# EnsembleThree.net
KiCad netlist of a schematic drawn in EAGLE
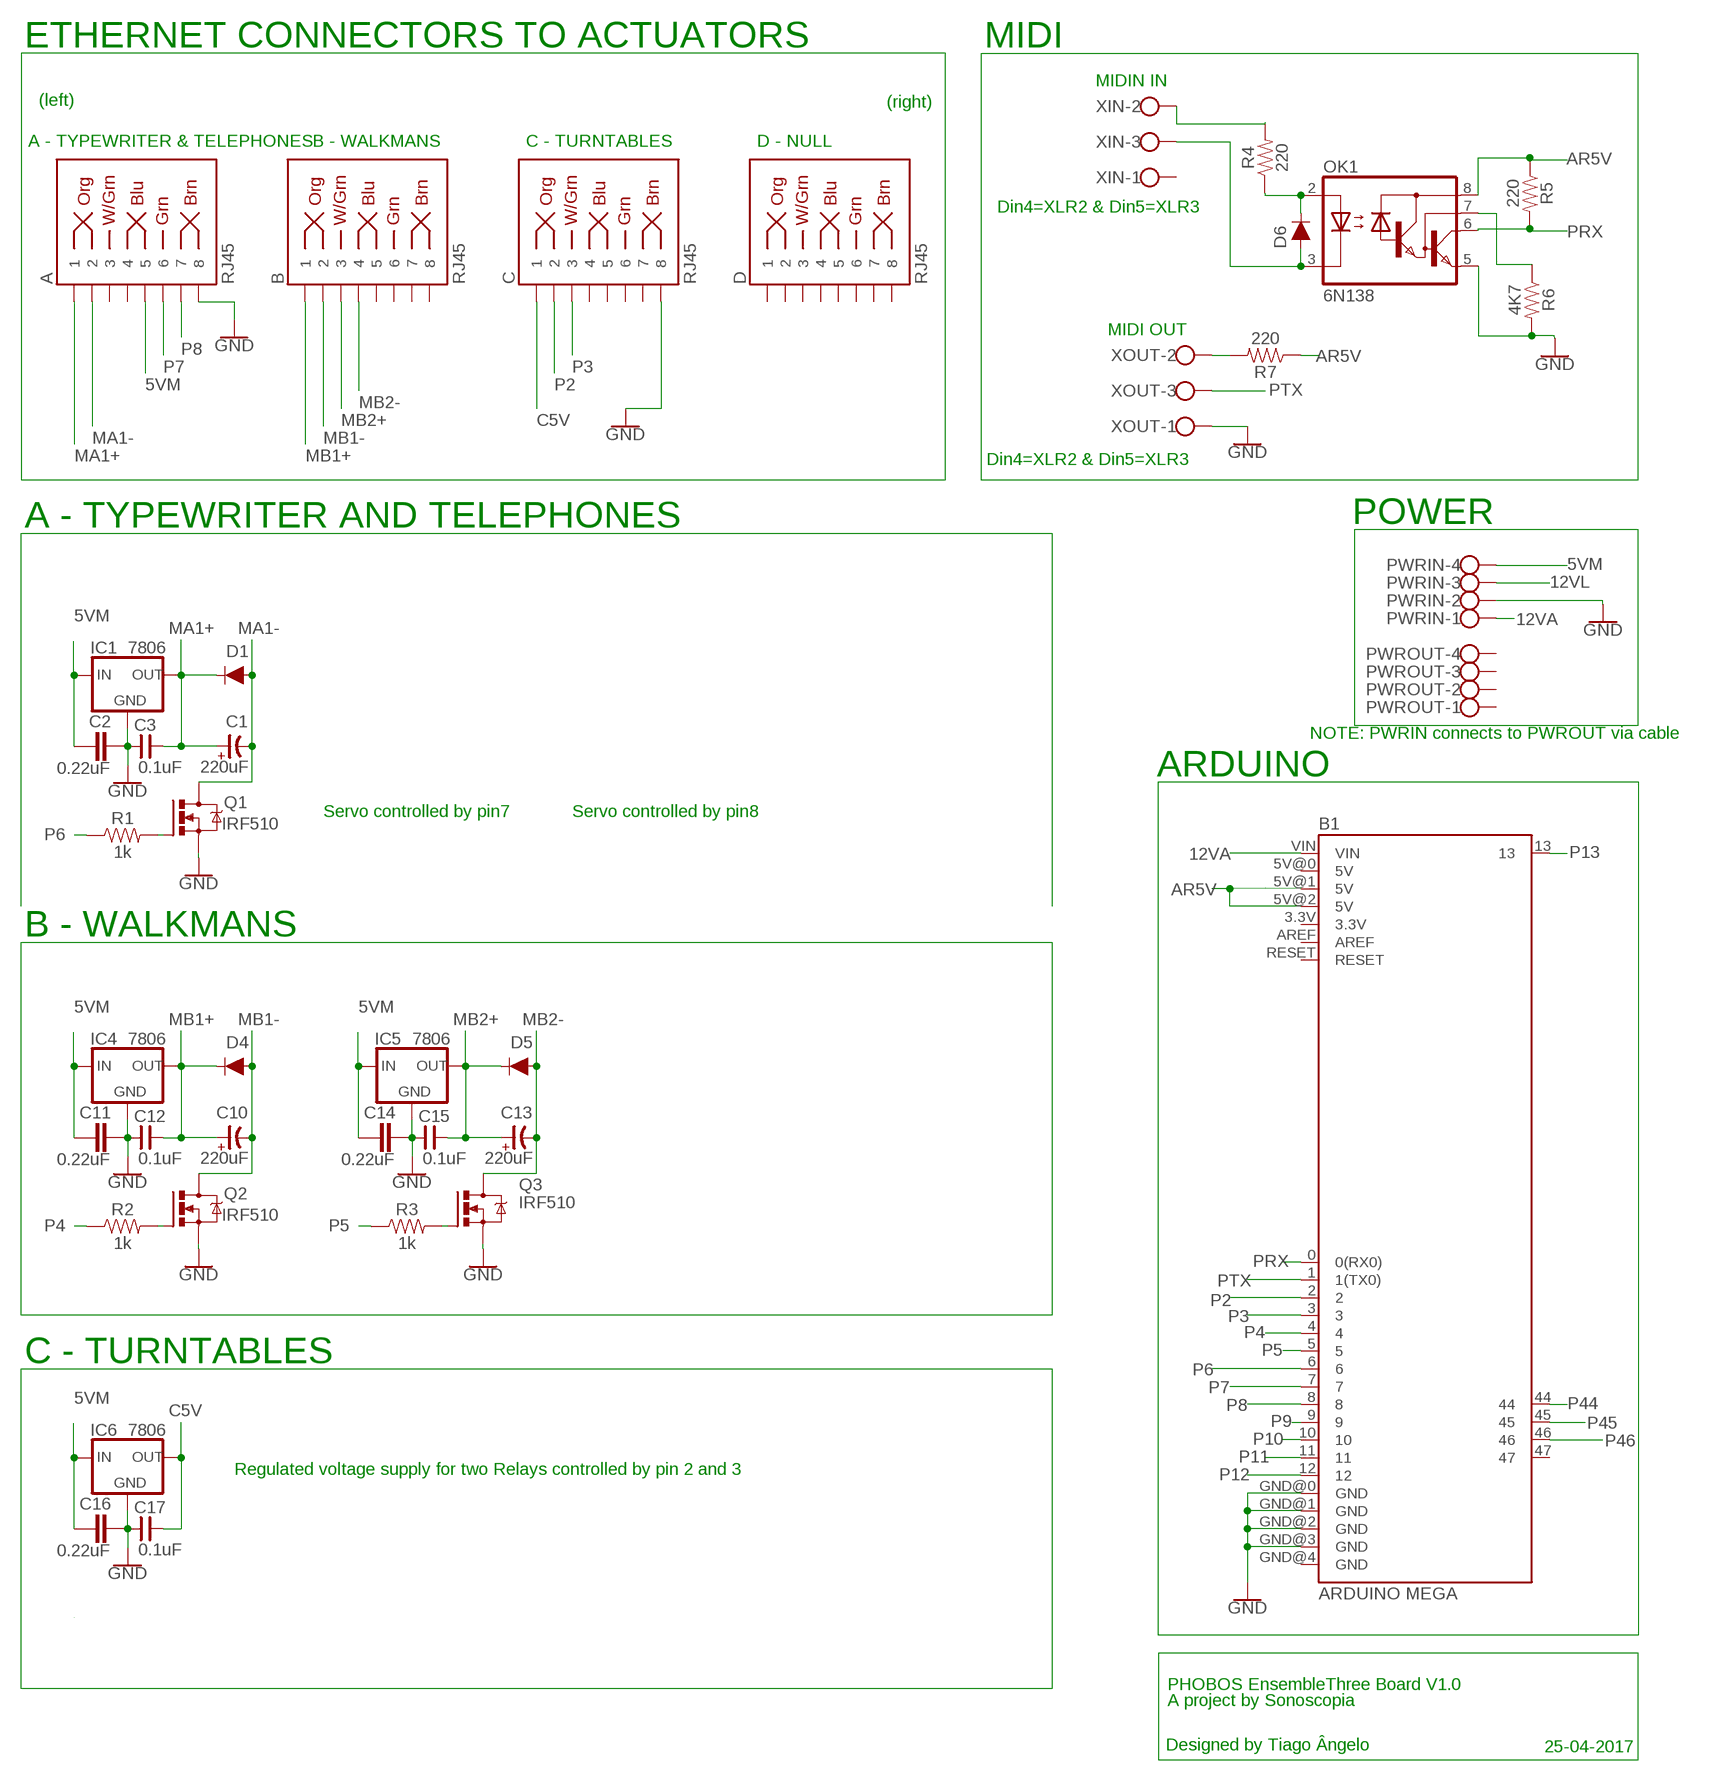
[diagram p0: schematic, sheet 1]

(export (version "E")
  (design (tool "Eeschema 10.0.6"))
  (components
    (comp (ref "A")
      (value "RJ45")
      (footprint "eagle-import:RJ45-8")
      (libsource (lib "eagle-import") (part "RJ45-8"))
    )
    (comp (ref "B")
      (value "RJ45")
      (footprint "eagle-import:RJ45-8")
      (libsource (lib "eagle-import") (part "RJ45-8"))
    )
    (comp (ref "B1")
      (value "ARDUINO MEGA")
      (footprint "eagle-import:ARDUINO_MEGA")
      (libsource (lib "eagle-import") (part "ARDUINO_MEGA_R3FULL"))
    )
    (comp (ref "C")
      (value "RJ45")
      (footprint "eagle-import:RJ45-8")
      (libsource (lib "eagle-import") (part "RJ45-8"))
    )
    (comp (ref "C1")
      (value "220uF")
      (footprint "eagle-import:E-035X080")
      (libsource (lib "eagle-import") (part "CP-E-035X080"))
    )
    (comp (ref "C2")
      (value "0.22uF")
      (footprint "eagle-import:C5B3")
      (libsource (lib "eagle-import") (part "C5/3"))
    )
    (comp (ref "C3")
      (value "0.1uF")
      (footprint "eagle-import:C025-050X025")
      (libsource (lib "eagle-import") (part "CNP-C025-050X025"))
    )
    (comp (ref "C10")
      (value "220uF")
      (footprint "eagle-import:E-035X080")
      (libsource (lib "eagle-import") (part "CP-E-035X080"))
    )
    (comp (ref "C11")
      (value "0.22uF")
      (footprint "eagle-import:C5B3")
      (libsource (lib "eagle-import") (part "C5/3"))
    )
    (comp (ref "C12")
      (value "0.1uF")
      (footprint "eagle-import:C025-050X025")
      (libsource (lib "eagle-import") (part "CNP-C025-050X025"))
    )
    (comp (ref "C13")
      (value "220uF")
      (footprint "eagle-import:CAP-MASTER_E-035X080")
      (libsource (lib "eagle-import") (part "CAP-MASTER_CP-E-035X080"))
    )
    (comp (ref "C14")
      (value "0.22uF")
      (footprint "eagle-import:C5B3")
      (libsource (lib "eagle-import") (part "C5/3"))
    )
    (comp (ref "C15")
      (value "0.1uF")
      (footprint "eagle-import:C025-050X025")
      (libsource (lib "eagle-import") (part "CNP-C025-050X025"))
    )
    (comp (ref "C16")
      (value "0.22uF")
      (footprint "eagle-import:C5B3")
      (libsource (lib "eagle-import") (part "C5/3"))
    )
    (comp (ref "C17")
      (value "0.1uF")
      (footprint "eagle-import:C025-050X025")
      (libsource (lib "eagle-import") (part "CNP-C025-050X025"))
    )
    (comp (ref "D")
      (value "RJ45")
      (footprint "eagle-import:RJ45-8")
      (libsource (lib "eagle-import") (part "RJ45-8"))
    )
    (comp (ref "D1")
      (value "1A/50V/1.1V")
      (footprint "eagle-import:DIODE-1N4001-KIT")
      (libsource (lib "eagle-import") (part "DIODE-KIT2"))
    )
    (comp (ref "D4")
      (value "1A/50V/1.1V")
      (footprint "eagle-import:DIODE-1N4001-KIT")
      (libsource (lib "eagle-import") (part "DIODE-KIT2"))
    )
    (comp (ref "D5")
      (value "1A/50V/1.1V")
      (footprint "eagle-import:DIODE-1N4001-KIT")
      (libsource (lib "eagle-import") (part "DIODE-KIT2"))
    )
    (comp (ref "D6")
      (value "200mA/100V/1V")
      (footprint "eagle-import:DIODE-1N4148")
      (libsource (lib "eagle-import") (part "DIODE-1N4148"))
    )
    (comp (ref "IC1")
      (value "7806")
      (footprint "eagle-import:78XXS")
      (libsource (lib "eagle-import") (part "78XXS"))
    )
    (comp (ref "IC4")
      (value "7806")
      (footprint "eagle-import:78XXS")
      (libsource (lib "eagle-import") (part "78XXS"))
    )
    (comp (ref "IC5")
      (value "7806")
      (footprint "eagle-import:78XXS")
      (libsource (lib "eagle-import") (part "78XXS"))
    )
    (comp (ref "IC6")
      (value "7806")
      (footprint "eagle-import:78XXS")
      (libsource (lib "eagle-import") (part "78XXS"))
    )
    (comp (ref "OK1")
      (value "6N138")
      (footprint "eagle-import:DIL08")
      (fields (field (name "MF") "VISHAY/TELEFUNKEN"))
      (libsource (lib "eagle-import") (part "6N138"))
    )
    (comp (ref "PWRIN")
      (value "W237-4")
      (footprint "eagle-import:W237-4")
      (libsource (lib "eagle-import") (part "W237-4"))
    )
    (comp (ref "PWROUT")
      (value "W237-4")
      (footprint "eagle-import:W237-4")
      (libsource (lib "eagle-import") (part "W237-4"))
    )
    (comp (ref "Q1")
      (value "IRF510")
      (footprint "eagle-import:TO220BV")
      (libsource (lib "eagle-import") (part "IRF520"))
    )
    (comp (ref "Q2")
      (value "IRF510")
      (footprint "eagle-import:TO220BV")
      (libsource (lib "eagle-import") (part "IRF520"))
    )
    (comp (ref "Q3")
      (value "IRF510")
      (footprint "eagle-import:TRANSISTOR-POWER_TO220BV")
      (libsource (lib "eagle-import") (part "TRANSISTOR-POWER_IRF520"))
    )
    (comp (ref "R1")
      (value "1k")
      (footprint "eagle-import:AXIAL-0.1")
      (libsource (lib "eagle-import") (part "1KOHM-VERT-1/4W-1%"))
    )
    (comp (ref "R2")
      (value "1k")
      (footprint "eagle-import:AXIAL-0.1")
      (libsource (lib "eagle-import") (part "1KOHM-VERT-1/4W-1%"))
    )
    (comp (ref "R3")
      (value "1k")
      (footprint "eagle-import:AXIAL-0.1")
      (libsource (lib "eagle-import") (part "1KOHM-VERT-1/4W-1%"))
    )
    (comp (ref "R4")
      (value "220")
      (footprint "eagle-import:AXIAL-0.3")
      (libsource (lib "eagle-import") (part "1KOHM-HORIZ-1/4W-5%"))
    )
    (comp (ref "R5")
      (value "220")
      (footprint "eagle-import:AXIAL-0.3")
      (libsource (lib "eagle-import") (part "1KOHM-HORIZ-1/4W-5%"))
    )
    (comp (ref "R6")
      (value "4K7")
      (footprint "eagle-import:AXIAL-0.3")
      (libsource (lib "eagle-import") (part "1KOHM-HORIZ-1/4W-5%"))
    )
    (comp (ref "R7")
      (value "220")
      (footprint "eagle-import:AXIAL-0.3")
      (libsource (lib "eagle-import") (part "1KOHM-HORIZ-1/4W-5%"))
    )
    (comp (ref "XIN")
      (value "W237-103")
      (footprint "eagle-import:W237-103")
      (fields (field (name "MPN") "237-103"))
      (libsource (lib "eagle-import") (part "W237-103"))
    )
    (comp (ref "XOUT")
      (value "W237-103")
      (footprint "eagle-import:W237-103")
      (fields (field (name "MPN") "237-103"))
      (libsource (lib "eagle-import") (part "W237-103"))
    )
  )
  (nets
    (net (code "1") (name "/5VM") (class "Default")
      (node (ref "A") (pin "5") (pinfunction "5_5") (pintype "bidirectional"))
      (node (ref "C11") (pin "1") (pinfunction "1_1") (pintype "passive"))
      (node (ref "C14") (pin "1") (pinfunction "1_1") (pintype "passive"))
      (node (ref "C16") (pin "1") (pinfunction "1_1") (pintype "passive"))
      (node (ref "C2") (pin "1") (pinfunction "1_1") (pintype "passive"))
      (node (ref "IC1") (pin "IN") (pinfunction "IN_IN") (pintype "input"))
      (node (ref "IC4") (pin "IN") (pinfunction "IN_IN") (pintype "input"))
      (node (ref "IC5") (pin "IN") (pinfunction "IN_IN") (pintype "input"))
      (node (ref "IC6") (pin "IN") (pinfunction "IN_IN") (pintype "input"))
      (node (ref "PWRIN") (pin "4") (pinfunction "KL_4") (pintype "passive"))
    )
    (net (code "2") (name "/12VA") (class "Default")
      (node (ref "B1") (pin "VIN") (pinfunction "VIN_VIN") (pintype "bidirectional"))
      (node (ref "PWRIN") (pin "1") (pinfunction "KL_1") (pintype "passive"))
    )
    (net (code "3") (name "/12VL") (class "Default")
      (node (ref "PWRIN") (pin "3") (pinfunction "KL_3") (pintype "passive"))
    )
    (net (code "4") (name "/AR5V") (class "Default")
      (node (ref "B1") (pin "5V@1") (pinfunction "5V_5V@1") (pintype "bidirectional"))
      (node (ref "B1") (pin "5V@2") (pinfunction "5V_5V@2") (pintype "bidirectional"))
      (node (ref "OK1") (pin "8") (pinfunction "VCC_8") (pintype "passive"))
      (node (ref "R5") (pin "P$1") (pinfunction "1_P$1") (pintype "passive"))
      (node (ref "R7") (pin "P$1") (pinfunction "1_P$1") (pintype "passive"))
    )
    (net (code "5") (name "/C5V") (class "Default")
      (node (ref "C") (pin "1") (pinfunction "1_1") (pintype "bidirectional"))
      (node (ref "C17") (pin "2") (pinfunction "2_2") (pintype "passive"))
      (node (ref "IC6") (pin "OUT") (pinfunction "OUT_OUT") (pintype "passive"))
    )
    (net (code "6") (name "/MA1+") (class "Default")
      (node (ref "A") (pin "1") (pinfunction "1_1") (pintype "bidirectional"))
      (node (ref "C1") (pin "+") (pinfunction "+_+") (pintype "passive"))
      (node (ref "C3") (pin "2") (pinfunction "2_2") (pintype "passive"))
      (node (ref "D1") (pin "C") (pinfunction "C_C") (pintype "passive"))
      (node (ref "IC1") (pin "OUT") (pinfunction "OUT_OUT") (pintype "passive"))
    )
    (net (code "7") (name "/MA1-") (class "Default")
      (node (ref "A") (pin "2") (pinfunction "2_2") (pintype "bidirectional"))
      (node (ref "C1") (pin "-") (pinfunction "-_-") (pintype "passive"))
      (node (ref "D1") (pin "A") (pinfunction "A_A") (pintype "passive"))
      (node (ref "Q1") (pin "D") (pinfunction "D_D") (pintype "passive"))
    )
    (net (code "8") (name "/MB1+") (class "Default")
      (node (ref "B") (pin "1") (pinfunction "1_1") (pintype "bidirectional"))
      (node (ref "C10") (pin "+") (pinfunction "+_+") (pintype "passive"))
      (node (ref "C12") (pin "2") (pinfunction "2_2") (pintype "passive"))
      (node (ref "D4") (pin "C") (pinfunction "C_C") (pintype "passive"))
      (node (ref "IC4") (pin "OUT") (pinfunction "OUT_OUT") (pintype "passive"))
    )
    (net (code "9") (name "/MB1-") (class "Default")
      (node (ref "B") (pin "2") (pinfunction "2_2") (pintype "bidirectional"))
      (node (ref "C10") (pin "-") (pinfunction "-_-") (pintype "passive"))
      (node (ref "D4") (pin "A") (pinfunction "A_A") (pintype "passive"))
      (node (ref "Q2") (pin "D") (pinfunction "D_D") (pintype "passive"))
    )
    (net (code "10") (name "/MB2+") (class "Default")
      (node (ref "B") (pin "3") (pinfunction "3_3") (pintype "bidirectional"))
      (node (ref "C13") (pin "+") (pinfunction "+_+") (pintype "passive"))
      (node (ref "C15") (pin "2") (pinfunction "2_2") (pintype "passive"))
      (node (ref "D5") (pin "C") (pinfunction "C_C") (pintype "passive"))
      (node (ref "IC5") (pin "OUT") (pinfunction "OUT_OUT") (pintype "passive"))
    )
    (net (code "11") (name "/MB2-") (class "Default")
      (node (ref "B") (pin "4") (pinfunction "4_4") (pintype "bidirectional"))
      (node (ref "C13") (pin "-") (pinfunction "-_-") (pintype "passive"))
      (node (ref "D5") (pin "A") (pinfunction "A_A") (pintype "passive"))
      (node (ref "Q3") (pin "D") (pinfunction "D_D") (pintype "passive"))
    )
    (net (code "12") (name "/P2") (class "Default")
      (node (ref "B1") (pin "2") (pinfunction "2_2") (pintype "bidirectional"))
      (node (ref "C") (pin "2") (pinfunction "2_2") (pintype "bidirectional"))
    )
    (net (code "13") (name "/P3") (class "Default")
      (node (ref "B1") (pin "3") (pinfunction "3_3") (pintype "bidirectional"))
      (node (ref "C") (pin "3") (pinfunction "3_3") (pintype "bidirectional"))
    )
    (net (code "14") (name "/P4") (class "Default")
      (node (ref "B1") (pin "4") (pinfunction "4_4") (pintype "bidirectional"))
      (node (ref "R2") (pin "P$1") (pinfunction "1_P$1") (pintype "passive"))
    )
    (net (code "15") (name "/P5") (class "Default")
      (node (ref "B1") (pin "5") (pinfunction "5_5") (pintype "bidirectional"))
      (node (ref "R3") (pin "P$1") (pinfunction "1_P$1") (pintype "passive"))
    )
    (net (code "16") (name "/P6") (class "Default")
      (node (ref "B1") (pin "6") (pinfunction "6_6") (pintype "bidirectional"))
      (node (ref "R1") (pin "P$1") (pinfunction "1_P$1") (pintype "passive"))
    )
    (net (code "17") (name "/P7") (class "Default")
      (node (ref "A") (pin "6") (pinfunction "6_6") (pintype "bidirectional"))
      (node (ref "B1") (pin "7") (pinfunction "7_7") (pintype "bidirectional"))
    )
    (net (code "18") (name "/P8") (class "Default")
      (node (ref "A") (pin "7") (pinfunction "7_7") (pintype "bidirectional"))
      (node (ref "B1") (pin "8") (pinfunction "8_8") (pintype "bidirectional"))
    )
    (net (code "19") (name "/P9") (class "Default")
      (node (ref "B1") (pin "9") (pinfunction "9_9") (pintype "bidirectional"))
    )
    (net (code "20") (name "/P10") (class "Default")
      (node (ref "B1") (pin "10") (pinfunction "10_10") (pintype "bidirectional"))
    )
    (net (code "21") (name "/P11") (class "Default")
      (node (ref "B1") (pin "11") (pinfunction "11_11") (pintype "bidirectional"))
    )
    (net (code "22") (name "/P12") (class "Default")
      (node (ref "B1") (pin "12") (pinfunction "12_12") (pintype "bidirectional"))
    )
    (net (code "23") (name "/P13") (class "Default")
      (node (ref "B1") (pin "13") (pinfunction "13_13") (pintype "bidirectional"))
    )
    (net (code "24") (name "/P44") (class "Default")
      (node (ref "B1") (pin "44") (pinfunction "44_44") (pintype "bidirectional"))
    )
    (net (code "25") (name "/P45") (class "Default")
      (node (ref "B1") (pin "45") (pinfunction "45_45") (pintype "bidirectional"))
    )
    (net (code "26") (name "/P46") (class "Default")
      (node (ref "B1") (pin "46") (pinfunction "46_46") (pintype "bidirectional"))
    )
    (net (code "27") (name "/PRX") (class "Default")
      (node (ref "B1") (pin "0") (pinfunction "0(RX0)_0") (pintype "bidirectional"))
      (node (ref "OK1") (pin "6") (pinfunction "VO_6") (pintype "passive"))
      (node (ref "R5") (pin "P$2") (pinfunction "2_P$2") (pintype "passive"))
    )
    (net (code "28") (name "/PTX") (class "Default")
      (node (ref "B1") (pin "1") (pinfunction "1(TX0)_1") (pintype "bidirectional"))
      (node (ref "XOUT") (pin "3") (pinfunction "KL_3") (pintype "passive"))
    )
    (net (code "29") (name "GND") (class "Default")
      (node (ref "A") (pin "8") (pinfunction "8_8") (pintype "bidirectional"))
      (node (ref "B1") (pin "GND@0") (pinfunction "GND_GND@0") (pintype "bidirectional"))
      (node (ref "B1") (pin "GND@1") (pinfunction "GND_GND@1") (pintype "bidirectional"))
      (node (ref "B1") (pin "GND@2") (pinfunction "GND_GND@2") (pintype "bidirectional"))
      (node (ref "B1") (pin "GND@3") (pinfunction "GND_GND@3") (pintype "bidirectional"))
      (node (ref "C") (pin "8") (pinfunction "8_8") (pintype "bidirectional"))
      (node (ref "C11") (pin "2") (pinfunction "2_2") (pintype "passive"))
      (node (ref "C12") (pin "1") (pinfunction "1_1") (pintype "passive"))
      (node (ref "C14") (pin "2") (pinfunction "2_2") (pintype "passive"))
      (node (ref "C15") (pin "1") (pinfunction "1_1") (pintype "passive"))
      (node (ref "C16") (pin "2") (pinfunction "2_2") (pintype "passive"))
      (node (ref "C17") (pin "1") (pinfunction "1_1") (pintype "passive"))
      (node (ref "C2") (pin "2") (pinfunction "2_2") (pintype "passive"))
      (node (ref "C3") (pin "1") (pinfunction "1_1") (pintype "passive"))
      (node (ref "IC1") (pin "GND") (pinfunction "GND_GND") (pintype "input"))
      (node (ref "IC4") (pin "GND") (pinfunction "GND_GND") (pintype "input"))
      (node (ref "IC5") (pin "GND") (pinfunction "GND_GND") (pintype "input"))
      (node (ref "IC6") (pin "GND") (pinfunction "GND_GND") (pintype "input"))
      (node (ref "OK1") (pin "5") (pinfunction "GND_5") (pintype "passive"))
      (node (ref "PWRIN") (pin "2") (pinfunction "KL_2") (pintype "passive"))
      (node (ref "Q1") (pin "S") (pinfunction "S_S") (pintype "passive"))
      (node (ref "Q2") (pin "S") (pinfunction "S_S") (pintype "passive"))
      (node (ref "Q3") (pin "S") (pinfunction "S_S") (pintype "passive"))
      (node (ref "R6") (pin "P$2") (pinfunction "2_P$2") (pintype "passive"))
      (node (ref "XOUT") (pin "1") (pinfunction "KL_1") (pintype "passive"))
    )
    (net (code "30") (name "Net-(OK1-A)") (class "Default")
      (node (ref "D6") (pin "C") (pinfunction "C_C") (pintype "passive"))
      (node (ref "OK1") (pin "2") (pinfunction "A_2") (pintype "passive"))
      (node (ref "R4") (pin "P$1") (pinfunction "1_P$1") (pintype "passive"))
    )
    (net (code "31") (name "Net-(OK1-C)") (class "Default")
      (node (ref "D6") (pin "A") (pinfunction "A_A") (pintype "passive"))
      (node (ref "OK1") (pin "3") (pinfunction "C_3") (pintype "passive"))
      (node (ref "XIN") (pin "3") (pinfunction "KL_3") (pintype "passive"))
    )
    (net (code "32") (name "Net-(OK1-VB)") (class "Default")
      (node (ref "OK1") (pin "7") (pinfunction "VB_7") (pintype "passive"))
      (node (ref "R6") (pin "P$1") (pinfunction "1_P$1") (pintype "passive"))
    )
    (net (code "33") (name "Net-(R1-2)") (class "Default")
      (node (ref "Q1") (pin "G") (pinfunction "G_G") (pintype "passive"))
      (node (ref "R1") (pin "P$2") (pinfunction "2_P$2") (pintype "passive"))
    )
    (net (code "34") (name "Net-(R2-2)") (class "Default")
      (node (ref "Q2") (pin "G") (pinfunction "G_G") (pintype "passive"))
      (node (ref "R2") (pin "P$2") (pinfunction "2_P$2") (pintype "passive"))
    )
    (net (code "35") (name "Net-(R3-2)") (class "Default")
      (node (ref "Q3") (pin "G") (pinfunction "G_G") (pintype "passive"))
      (node (ref "R3") (pin "P$2") (pinfunction "2_P$2") (pintype "passive"))
    )
    (net (code "36") (name "Net-(R4-2)") (class "Default")
      (node (ref "R4") (pin "P$2") (pinfunction "2_P$2") (pintype "passive"))
      (node (ref "XIN") (pin "2") (pinfunction "KL_2") (pintype "passive"))
    )
    (net (code "37") (name "Net-(R7-2)") (class "Default")
      (node (ref "R7") (pin "P$2") (pinfunction "2_P$2") (pintype "passive"))
      (node (ref "XOUT") (pin "2") (pinfunction "KL_2") (pintype "passive"))
    )
    (net (code "38") (name "unconnected-(A-Pad3)") (class "Default")
      (node (ref "A") (pin "3") (pinfunction "3_3") (pintype "bidirectional"))
    )
    (net (code "39") (name "unconnected-(A-Pad4)") (class "Default")
      (node (ref "A") (pin "4") (pinfunction "4_4") (pintype "bidirectional"))
    )
    (net (code "40") (name "unconnected-(B-Pad5)") (class "Default")
      (node (ref "B") (pin "5") (pinfunction "5_5") (pintype "bidirectional"))
    )
    (net (code "41") (name "unconnected-(B-Pad6)") (class "Default")
      (node (ref "B") (pin "6") (pinfunction "6_6") (pintype "bidirectional"))
    )
    (net (code "42") (name "unconnected-(B-Pad7)") (class "Default")
      (node (ref "B") (pin "7") (pinfunction "7_7") (pintype "bidirectional"))
    )
    (net (code "43") (name "unconnected-(B-Pad8)") (class "Default")
      (node (ref "B") (pin "8") (pinfunction "8_8") (pintype "bidirectional"))
    )
    (net (code "44") (name "unconnected-(B1-5V-Pad5V@0)") (class "Default")
      (node (ref "B1") (pin "5V@0") (pinfunction "5V_5V@0") (pintype "bidirectional"))
    )
    (net (code "45") (name "unconnected-(B1-GND-PadGND@4)") (class "Default")
      (node (ref "B1") (pin "GND@4") (pinfunction "GND_GND@4") (pintype "bidirectional"))
    )
    (net (code "46") (name "unconnected-(B1-Pad3.3V)") (class "Default")
      (node (ref "B1") (pin "3.3V") (pinfunction "3.3V_3.3V") (pintype "bidirectional"))
    )
    (net (code "47") (name "unconnected-(B1-Pad47)") (class "Default")
      (node (ref "B1") (pin "47") (pinfunction "47_47") (pintype "bidirectional"))
    )
    (net (code "48") (name "unconnected-(B1-PadAREF)") (class "Default")
      (node (ref "B1") (pin "AREF") (pinfunction "AREF_AREF") (pintype "bidirectional"))
    )
    (net (code "49") (name "unconnected-(B1-PadRESET)") (class "Default")
      (node (ref "B1") (pin "RESET") (pinfunction "RESET_RESET") (pintype "bidirectional"))
    )
    (net (code "50") (name "unconnected-(C-Pad4)") (class "Default")
      (node (ref "C") (pin "4") (pinfunction "4_4") (pintype "bidirectional"))
    )
    (net (code "51") (name "unconnected-(C-Pad5)") (class "Default")
      (node (ref "C") (pin "5") (pinfunction "5_5") (pintype "bidirectional"))
    )
    (net (code "52") (name "unconnected-(C-Pad6)") (class "Default")
      (node (ref "C") (pin "6") (pinfunction "6_6") (pintype "bidirectional"))
    )
    (net (code "53") (name "unconnected-(C-Pad7)") (class "Default")
      (node (ref "C") (pin "7") (pinfunction "7_7") (pintype "bidirectional"))
    )
    (net (code "54") (name "unconnected-(D-Pad1)") (class "Default")
      (node (ref "D") (pin "1") (pinfunction "1_1") (pintype "bidirectional"))
    )
    (net (code "55") (name "unconnected-(D-Pad2)") (class "Default")
      (node (ref "D") (pin "2") (pinfunction "2_2") (pintype "bidirectional"))
    )
    (net (code "56") (name "unconnected-(D-Pad3)") (class "Default")
      (node (ref "D") (pin "3") (pinfunction "3_3") (pintype "bidirectional"))
    )
    (net (code "57") (name "unconnected-(D-Pad4)") (class "Default")
      (node (ref "D") (pin "4") (pinfunction "4_4") (pintype "bidirectional"))
    )
    (net (code "58") (name "unconnected-(D-Pad5)") (class "Default")
      (node (ref "D") (pin "5") (pinfunction "5_5") (pintype "bidirectional"))
    )
    (net (code "59") (name "unconnected-(D-Pad6)") (class "Default")
      (node (ref "D") (pin "6") (pinfunction "6_6") (pintype "bidirectional"))
    )
    (net (code "60") (name "unconnected-(D-Pad7)") (class "Default")
      (node (ref "D") (pin "7") (pinfunction "7_7") (pintype "bidirectional"))
    )
    (net (code "61") (name "unconnected-(D-Pad8)") (class "Default")
      (node (ref "D") (pin "8") (pinfunction "8_8") (pintype "bidirectional"))
    )
    (net (code "62") (name "unconnected-(PWROUTA-KL-Pad1)") (class "Default")
      (node (ref "PWROUT") (pin "1") (pinfunction "KL_1") (pintype "passive"))
    )
    (net (code "63") (name "unconnected-(PWROUTB-KL-Pad2)") (class "Default")
      (node (ref "PWROUT") (pin "2") (pinfunction "KL_2") (pintype "passive"))
    )
    (net (code "64") (name "unconnected-(PWROUTC-KL-Pad3)") (class "Default")
      (node (ref "PWROUT") (pin "3") (pinfunction "KL_3") (pintype "passive"))
    )
    (net (code "65") (name "unconnected-(PWROUTD-KL-Pad4)") (class "Default")
      (node (ref "PWROUT") (pin "4") (pinfunction "KL_4") (pintype "passive"))
    )
    (net (code "66") (name "unconnected-(XINA-KL-Pad1)") (class "Default")
      (node (ref "XIN") (pin "1") (pinfunction "KL_1") (pintype "passive"))
    )
  )
)
